# MPL3115A2_v0_2.net
KiCad netlist of a schematic drawn in EAGLE
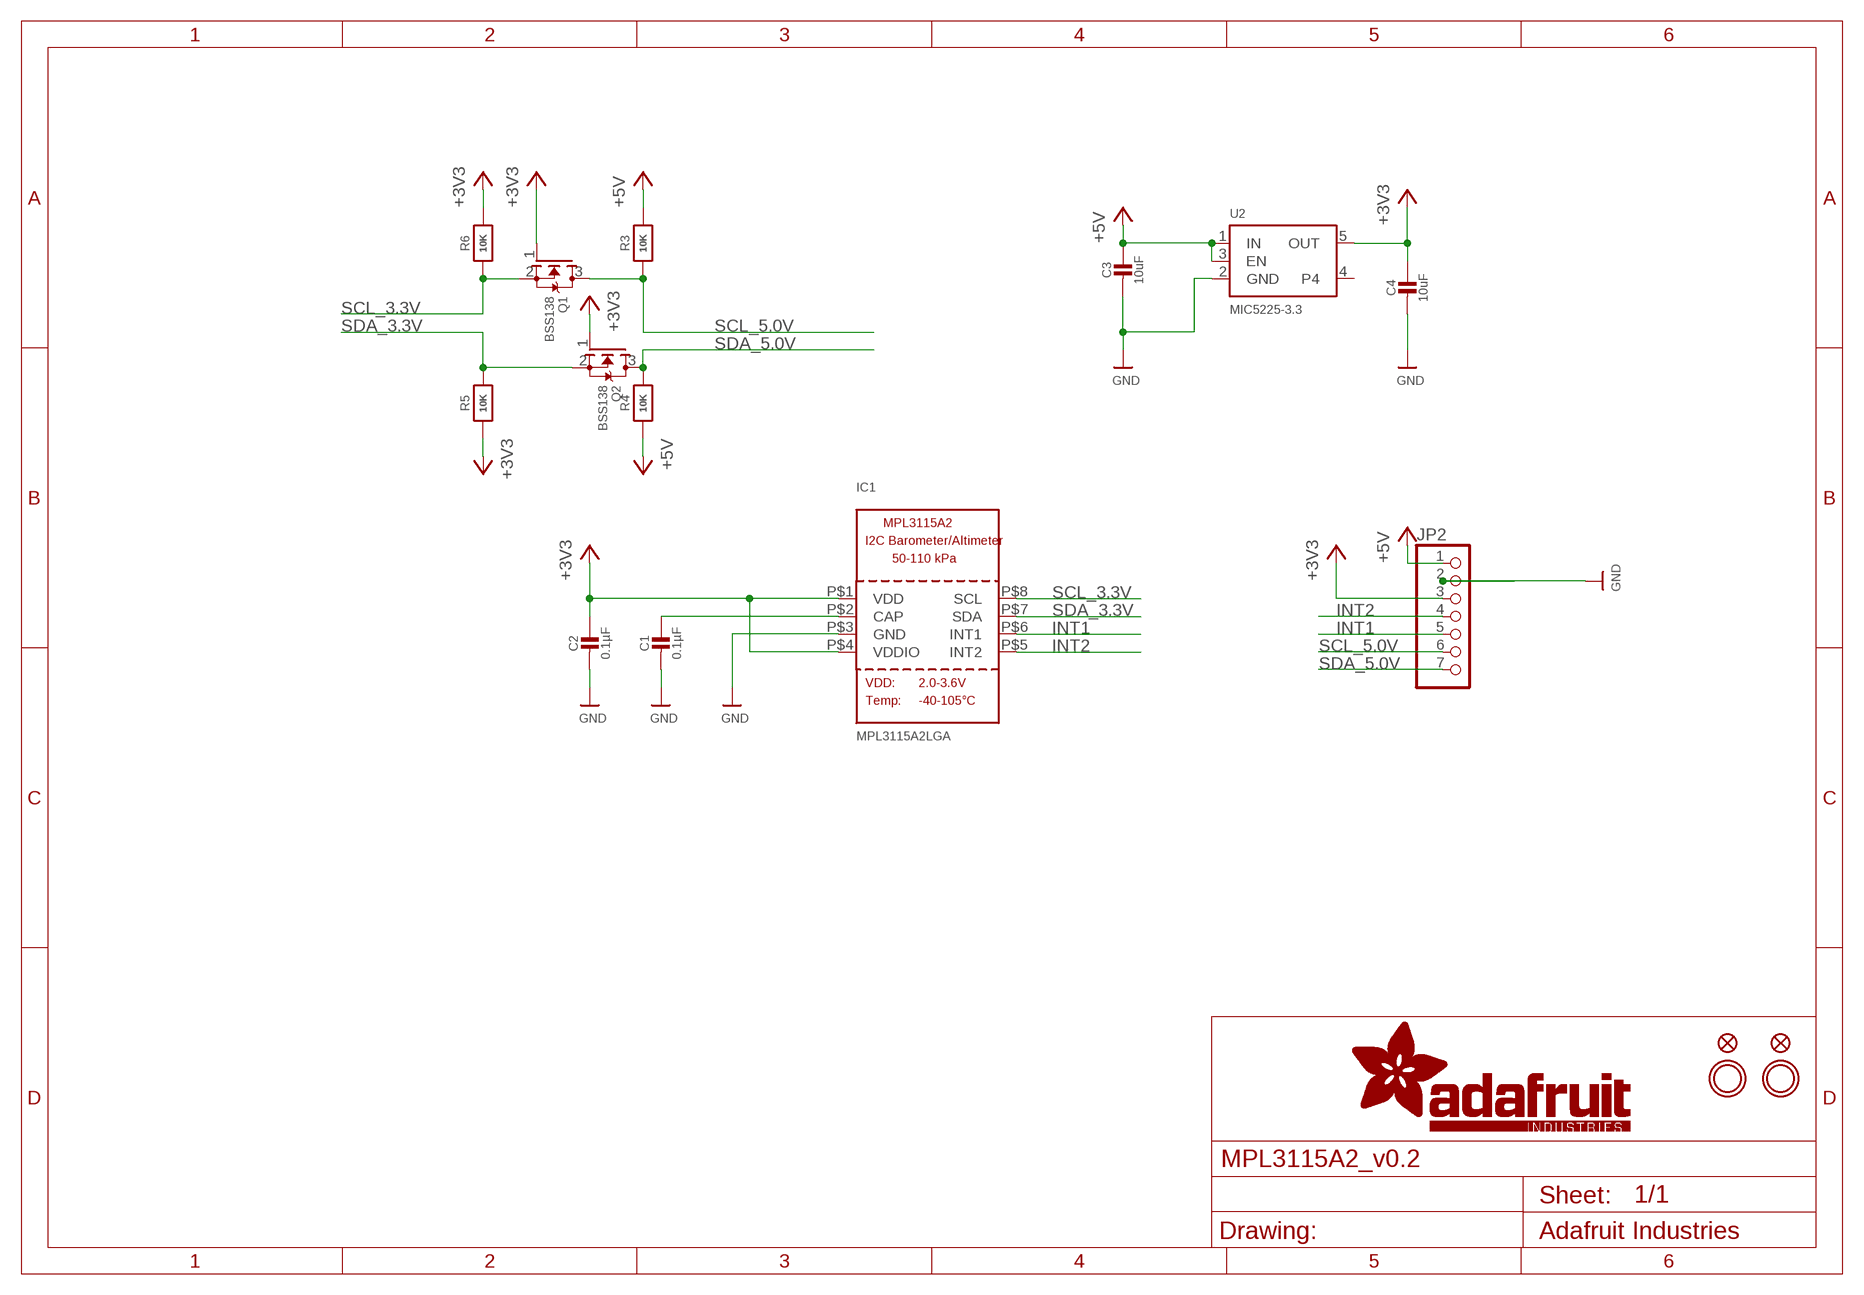
[diagram p0: schematic, sheet 1]

(export (version "E")
  (design (tool "Eeschema 10.0.6"))
  (components
    (comp (ref "C1")
      (value "0.1µF")
      (footprint "eagle-import:0805-NO")
      (libsource (lib "eagle-import") (part "CAP_CERAMIC0805-NOOUTLINE"))
    )
    (comp (ref "C2")
      (value "0.1µF")
      (footprint "eagle-import:0805-NO")
      (libsource (lib "eagle-import") (part "CAP_CERAMIC0805-NOOUTLINE"))
    )
    (comp (ref "C3")
      (value "10uF")
      (footprint "eagle-import:0805-NO")
      (libsource (lib "eagle-import") (part "CAP_CERAMIC0805-NOOUTLINE"))
    )
    (comp (ref "C4")
      (value "10uF")
      (footprint "eagle-import:0805-NO")
      (libsource (lib "eagle-import") (part "CAP_CERAMIC0805-NOOUTLINE"))
    )
    (comp (ref "FID1")
      (value "FIDUCIAL\"\"")
      (footprint "eagle-import:FIDUCIAL_1MM")
      (libsource (lib "eagle-import") (part "FIDUCIAL{dblquote}{dblquote}"))
    )
    (comp (ref "FID2")
      (value "FIDUCIAL\"\"")
      (footprint "eagle-import:FIDUCIAL_1MM")
      (libsource (lib "eagle-import") (part "FIDUCIAL{dblquote}{dblquote}"))
    )
    (comp (ref "IC1")
      (value "MPL3115A2LGA")
      (footprint "eagle-import:LGA8")
      (libsource (lib "eagle-import") (part "MPL3115A2LGA"))
    )
    (comp (ref "JP2")
      (value "HEADER-1X770MIL")
      (footprint "eagle-import:1X07_ROUND_70")
      (libsource (lib "eagle-import") (part "HEADER-1X770MIL"))
    )
    (comp (ref "Q1")
      (value "BSS138")
      (footprint "eagle-import:SOT23-WIDE")
      (libsource (lib "eagle-import") (part "MOSFET-NWIDE"))
    )
    (comp (ref "Q2")
      (value "BSS138")
      (footprint "eagle-import:SOT23-WIDE")
      (libsource (lib "eagle-import") (part "MOSFET-NWIDE"))
    )
    (comp (ref "R3")
      (value "10K")
      (footprint "eagle-import:0805-NO")
      (libsource (lib "eagle-import") (part "RESISTOR0805_NOOUTLINE"))
    )
    (comp (ref "R4")
      (value "10K")
      (footprint "eagle-import:0805-NO")
      (libsource (lib "eagle-import") (part "RESISTOR0805_NOOUTLINE"))
    )
    (comp (ref "R5")
      (value "10K")
      (footprint "eagle-import:0805-NO")
      (libsource (lib "eagle-import") (part "RESISTOR0805_NOOUTLINE"))
    )
    (comp (ref "R6")
      (value "10K")
      (footprint "eagle-import:0805-NO")
      (libsource (lib "eagle-import") (part "RESISTOR0805_NOOUTLINE"))
    )
    (comp (ref "U$8")
      (value "MOUNTINGHOLE2.5")
      (footprint "eagle-import:MOUNTINGHOLE_2.5_PLATED")
      (libsource (lib "eagle-import") (part "MOUNTINGHOLE2.5"))
    )
    (comp (ref "U$9")
      (value "MOUNTINGHOLE2.5")
      (footprint "eagle-import:MOUNTINGHOLE_2.5_PLATED")
      (libsource (lib "eagle-import") (part "MOUNTINGHOLE2.5"))
    )
    (comp (ref "U2")
      (value "MIC5225-3.3")
      (footprint "eagle-import:SOT23-5")
      (libsource (lib "eagle-import") (part "VREG_SOT23-5"))
    )
  )
  (nets
    (net (code "1") (name "+3V3") (class "Default")
      (node (ref "C2") (pin "1") (pinfunction "1_1") (pintype "passive"))
      (node (ref "C4") (pin "1") (pinfunction "1_1") (pintype "passive"))
      (node (ref "IC1") (pin "P$1") (pinfunction "VDD_P$1") (pintype "power_in"))
      (node (ref "IC1") (pin "P$4") (pinfunction "VDDIO_P$4") (pintype "power_in"))
      (node (ref "JP2") (pin "3") (pinfunction "3_3") (pintype "passive"))
      (node (ref "Q1") (pin "1") (pinfunction "G_1") (pintype "bidirectional"))
      (node (ref "Q2") (pin "1") (pinfunction "G_1") (pintype "bidirectional"))
      (node (ref "R5") (pin "1") (pinfunction "1_1") (pintype "passive"))
      (node (ref "R6") (pin "2") (pinfunction "2_2") (pintype "passive"))
      (node (ref "U2") (pin "5") (pinfunction "OUT_5") (pintype "power_in"))
    )
    (net (code "2") (name "+5V") (class "Default")
      (node (ref "C3") (pin "1") (pinfunction "1_1") (pintype "passive"))
      (node (ref "JP2") (pin "1") (pinfunction "1_1") (pintype "passive"))
      (node (ref "R3") (pin "2") (pinfunction "2_2") (pintype "passive"))
      (node (ref "R4") (pin "1") (pinfunction "1_1") (pintype "passive"))
      (node (ref "U2") (pin "1") (pinfunction "IN_1") (pintype "power_in"))
      (node (ref "U2") (pin "3") (pinfunction "EN_3") (pintype "input"))
    )
    (net (code "3") (name "/INT1") (class "Default")
      (node (ref "IC1") (pin "P$6") (pinfunction "INT1_P$6") (pintype "output"))
      (node (ref "JP2") (pin "5") (pinfunction "5_5") (pintype "passive"))
    )
    (net (code "4") (name "/INT2") (class "Default")
      (node (ref "IC1") (pin "P$5") (pinfunction "INT2_P$5") (pintype "output"))
      (node (ref "JP2") (pin "4") (pinfunction "4_4") (pintype "passive"))
    )
    (net (code "5") (name "/SCL_3.3V") (class "Default")
      (node (ref "IC1") (pin "P$8") (pinfunction "SCL_P$8") (pintype "bidirectional"))
      (node (ref "Q1") (pin "2") (pinfunction "S_2") (pintype "bidirectional"))
      (node (ref "R6") (pin "1") (pinfunction "1_1") (pintype "passive"))
    )
    (net (code "6") (name "/SCL_5.0V") (class "Default")
      (node (ref "JP2") (pin "6") (pinfunction "6_6") (pintype "passive"))
      (node (ref "Q1") (pin "3") (pinfunction "D_3") (pintype "bidirectional"))
      (node (ref "R3") (pin "1") (pinfunction "1_1") (pintype "passive"))
    )
    (net (code "7") (name "/SDA_3.3V") (class "Default")
      (node (ref "IC1") (pin "P$7") (pinfunction "SDA_P$7") (pintype "bidirectional"))
      (node (ref "Q2") (pin "2") (pinfunction "S_2") (pintype "bidirectional"))
      (node (ref "R5") (pin "2") (pinfunction "2_2") (pintype "passive"))
    )
    (net (code "8") (name "/SDA_5.0V") (class "Default")
      (node (ref "JP2") (pin "7") (pinfunction "7_7") (pintype "passive"))
      (node (ref "Q2") (pin "3") (pinfunction "D_3") (pintype "bidirectional"))
      (node (ref "R4") (pin "2") (pinfunction "2_2") (pintype "passive"))
    )
    (net (code "9") (name "GND") (class "Default")
      (node (ref "C1") (pin "2") (pinfunction "2_2") (pintype "passive"))
      (node (ref "C2") (pin "2") (pinfunction "2_2") (pintype "passive"))
      (node (ref "C3") (pin "2") (pinfunction "2_2") (pintype "passive"))
      (node (ref "C4") (pin "2") (pinfunction "2_2") (pintype "passive"))
      (node (ref "IC1") (pin "P$3") (pinfunction "GND_P$3") (pintype "power_in"))
      (node (ref "JP2") (pin "2") (pinfunction "2_2") (pintype "passive"))
      (node (ref "U2") (pin "2") (pinfunction "GND_2") (pintype "power_in"))
    )
    (net (code "10") (name "Net-(IC1-CAP)") (class "Default")
      (node (ref "C1") (pin "1") (pinfunction "1_1") (pintype "passive"))
      (node (ref "IC1") (pin "P$2") (pinfunction "CAP_P$2") (pintype "passive"))
    )
    (net (code "11") (name "unconnected-(U2-P4-Pad4)") (class "Default")
      (node (ref "U2") (pin "4") (pinfunction "P4_4") (pintype "bidirectional"))
    )
  )
)
